# MidiMon.net
KiCad netlist of a schematic drawn in EAGLE
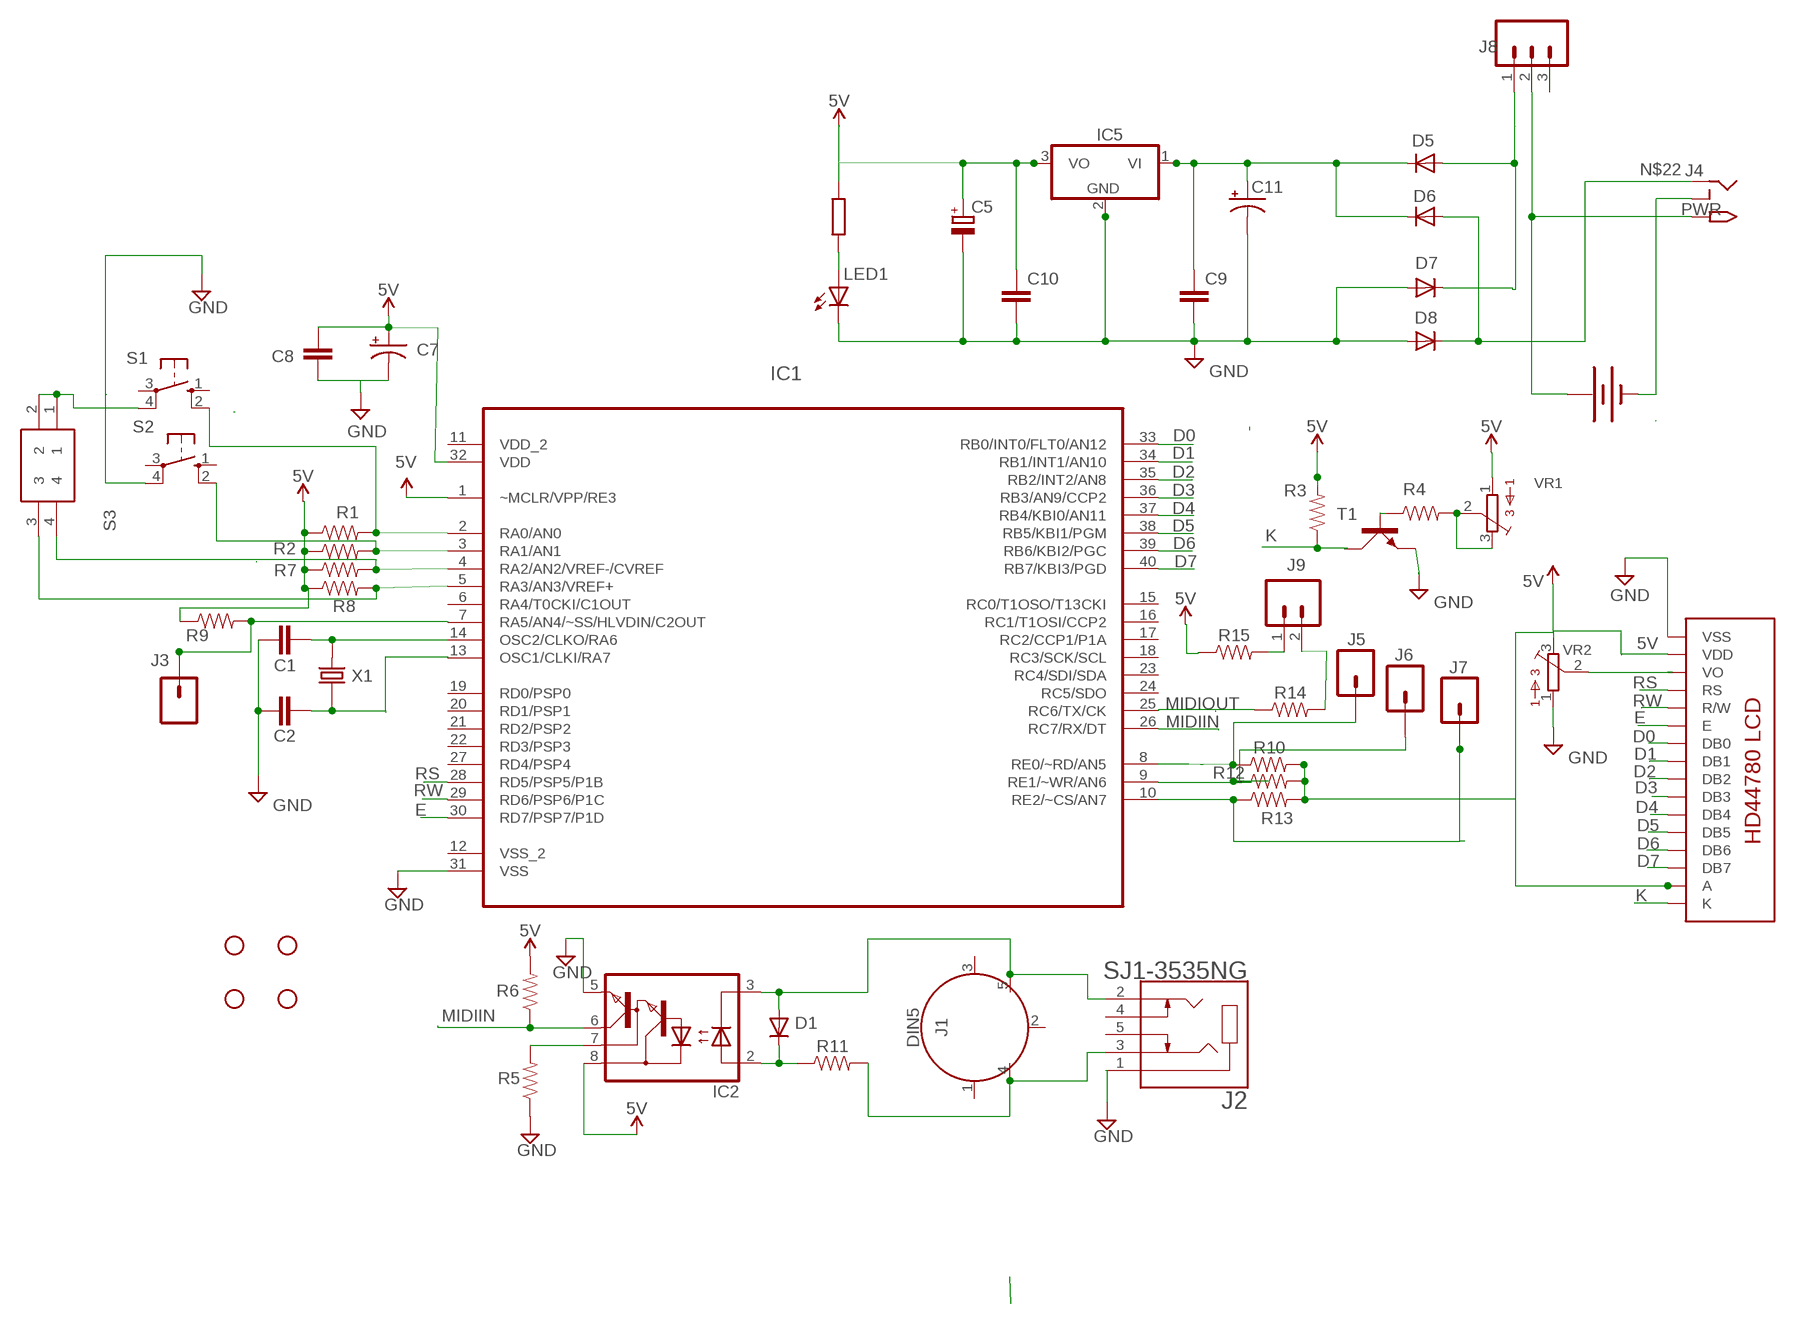
[diagram p0: schematic, sheet 1]

(export (version "E")
  (design (tool "Eeschema 10.0.6"))
  (components
    (comp (ref "BAT1")
      (value "BATTERY")
      (footprint "eagle-import:PP3_BATTERBOX")
      (libsource (lib "eagle-import") (part "BATTERY"))
    )
    (comp (ref "C1")
      (value "33pF")
      (footprint "eagle-import:CAP-PTH-2.54")
      (libsource (lib "eagle-import") (part "22PF-PTH-2.54MM-200V-5%"))
    )
    (comp (ref "C2")
      (value "33pF")
      (footprint "eagle-import:CAP-PTH-2.54")
      (libsource (lib "eagle-import") (part "22PF-PTH-2.54MM-200V-5%"))
    )
    (comp (ref "C5")
      (value "10uf")
      (footprint "eagle-import:E2,5-7")
      (libsource (lib "eagle-import") (part "CPOL-EUE2.5-7"))
    )
    (comp (ref "C7")
      (value "10uF")
      (footprint "eagle-import:CPOL-RADIAL-2.5MM-5MM")
      (libsource (lib "eagle-import") (part "10UF-POLAR-RADIAL-2.5MM-25V-20%"))
    )
    (comp (ref "C8")
      (value "0.1uF")
      (footprint "eagle-import:CAP-PTH-SMALL-KIT")
      (libsource (lib "eagle-import") (part "0.1UF-KIT-EZ-50V-20%"))
    )
    (comp (ref "C9")
      (value "330nf")
      (footprint "eagle-import:C025-024X044")
      (libsource (lib "eagle-import") (part "C-EU025-024X044"))
    )
    (comp (ref "C10")
      (value "100nf")
      (footprint "eagle-import:C025-024X044")
      (libsource (lib "eagle-import") (part "C-EU025-024X044"))
    )
    (comp (ref "C11")
      (value "2200uf")
      (footprint "eagle-import:E5-10,5")
      (libsource (lib "eagle-import") (part "CPOL-USE5-10.5"))
    )
    (comp (ref "D1")
      (value "DIODEDO-1N4148")
      (footprint "eagle-import:DO-1N4148")
      (libsource (lib "eagle-import") (part "DIODEDO-1N4148"))
    )
    (comp (ref "D5")
      (value "1N4004")
      (footprint "eagle-import:DO-VERT")
      (libsource (lib "eagle-import") (part "1N4004"))
    )
    (comp (ref "D6")
      (value "1N4004")
      (footprint "eagle-import:DO-VERT")
      (libsource (lib "eagle-import") (part "1N4004"))
    )
    (comp (ref "D7")
      (value "1N4004")
      (footprint "eagle-import:DO-VERT")
      (libsource (lib "eagle-import") (part "1N4004"))
    )
    (comp (ref "D8")
      (value "1N4004")
      (footprint "eagle-import:DO-VERT")
      (libsource (lib "eagle-import") (part "1N4004"))
    )
    (comp (ref "H1")
      (value "STAND-OFFTIGHT")
      (footprint "eagle-import:STAND-OFF-TIGHT")
      (libsource (lib "eagle-import") (part "STAND-OFFTIGHT"))
    )
    (comp (ref "H2")
      (value "STAND-OFFTIGHT")
      (footprint "eagle-import:STAND-OFF-TIGHT")
      (libsource (lib "eagle-import") (part "STAND-OFFTIGHT"))
    )
    (comp (ref "H3")
      (value "STAND-OFFTIGHT")
      (footprint "eagle-import:STAND-OFF-TIGHT")
      (libsource (lib "eagle-import") (part "STAND-OFFTIGHT"))
    )
    (comp (ref "H4")
      (value "STAND-OFFTIGHT")
      (footprint "eagle-import:STAND-OFF-TIGHT")
      (libsource (lib "eagle-import") (part "STAND-OFFTIGHT"))
    )
    (comp (ref "IC1")
      (value "PIC18F4520-I/P")
      (footprint "eagle-import:DIP254P1524X533-40")
      (fields (field (name "MF") "Microchip"))
      (libsource (lib "eagle-import") (part "PIC18F4520-I/P"))
    )
    (comp (ref "IC2")
      (value "6N138")
      (footprint "eagle-import:DIL08")
      (fields (field (name "MF") "VISHAY/TELEFUNKEN"))
      (libsource (lib "eagle-import") (part "6N138"))
    )
    (comp (ref "IC5")
      (value "7805TV")
      (footprint "eagle-import:TO220V")
      (libsource (lib "eagle-import") (part "78TV05"))
    )
    (comp (ref "J1")
      (value "DIN5")
      (footprint "eagle-import:DIN5-RA-PTH")
      (libsource (lib "eagle-import") (part "DIN5"))
    )
    (comp (ref "J2")
      (value "SJ1-3535NG")
      (footprint "eagle-import:CUI_SJ1-3535NG")
      (fields (field (name "MF") "CUI Inc."))
      (libsource (lib "eagle-import") (part "SJ1-3535NG"))
    )
    (comp (ref "J3")
      (value "CONN_01")
      (footprint "eagle-import:1X01")
      (libsource (lib "eagle-import") (part "CONN_01"))
    )
    (comp (ref "J4")
      (value "2.1MMJACKTHM")
      (footprint "eagle-import:PJ-102A")
      (libsource (lib "eagle-import") (part "2.1MMJACKTHM"))
    )
    (comp (ref "J5")
      (value "CONN_01")
      (footprint "eagle-import:1X01")
      (libsource (lib "eagle-import") (part "CONN_01"))
    )
    (comp (ref "J6")
      (value "CONN_01")
      (footprint "eagle-import:1X01")
      (libsource (lib "eagle-import") (part "CONN_01"))
    )
    (comp (ref "J7")
      (value "CONN_01")
      (footprint "eagle-import:1X01")
      (libsource (lib "eagle-import") (part "CONN_01"))
    )
    (comp (ref "J8")
      (value "CONN_03")
      (footprint "eagle-import:1X03")
      (libsource (lib "eagle-import") (part "CONN_03"))
    )
    (comp (ref "J9")
      (value "CONN_02")
      (footprint "eagle-import:1X02")
      (libsource (lib "eagle-import") (part "CONN_02"))
    )
    (comp (ref "LED1")
      (value "LED3MM")
      (footprint "eagle-import:LED3MM")
      (libsource (lib "eagle-import") (part "LED3MM"))
    )
    (comp (ref "R1")
      (value "10k")
      (footprint "eagle-import:AXIAL-0.3")
      (libsource (lib "eagle-import") (part "1KOHM-HORIZ-1/4W-5%"))
    )
    (comp (ref "R2")
      (value "10k")
      (footprint "eagle-import:AXIAL-0.3")
      (libsource (lib "eagle-import") (part "1KOHM-HORIZ-1/4W-5%"))
    )
    (comp (ref "R3")
      (value "10k")
      (footprint "eagle-import:AXIAL-0.3")
      (libsource (lib "eagle-import") (part "1KOHM-HORIZ-1/4W-5%"))
    )
    (comp (ref "R4")
      (value "1k")
      (footprint "eagle-import:AXIAL-0.3")
      (libsource (lib "eagle-import") (part "1KOHM-HORIZ-1/4W-5%"))
    )
    (comp (ref "R5")
      (value "5.6k")
      (footprint "eagle-import:AXIAL-0.3")
      (libsource (lib "eagle-import") (part "1KOHM-HORIZ-1/4W-5%"))
    )
    (comp (ref "R6")
      (value "1.2k")
      (footprint "eagle-import:AXIAL-0.3")
      (libsource (lib "eagle-import") (part "1KOHM-HORIZ-1/4W-5%"))
    )
    (comp (ref "R7")
      (value "10k")
      (footprint "eagle-import:AXIAL-0.3")
      (libsource (lib "eagle-import") (part "1KOHM-HORIZ-1/4W-5%"))
    )
    (comp (ref "R8")
      (value "10k")
      (footprint "eagle-import:AXIAL-0.3")
      (libsource (lib "eagle-import") (part "1KOHM-HORIZ-1/4W-5%"))
    )
    (comp (ref "R9")
      (value "10k")
      (footprint "eagle-import:AXIAL-0.3")
      (libsource (lib "eagle-import") (part "1KOHM-HORIZ-1/4W-5%"))
    )
    (comp (ref "R10")
      (value "10k")
      (footprint "eagle-import:AXIAL-0.3")
      (libsource (lib "eagle-import") (part "1KOHM-HORIZ-1/4W-5%"))
    )
    (comp (ref "R11")
      (value "220")
      (footprint "eagle-import:AXIAL-0.3")
      (libsource (lib "eagle-import") (part "1KOHM-HORIZ-1/4W-5%"))
    )
    (comp (ref "R12")
      (value "10k")
      (footprint "eagle-import:AXIAL-0.3")
      (libsource (lib "eagle-import") (part "1KOHM-HORIZ-1/4W-5%"))
    )
    (comp (ref "R13")
      (value "10k")
      (footprint "eagle-import:AXIAL-0.3")
      (libsource (lib "eagle-import") (part "1KOHM-HORIZ-1/4W-5%"))
    )
    (comp (ref "R14")
      (value "220")
      (footprint "eagle-import:AXIAL-0.3")
      (libsource (lib "eagle-import") (part "1KOHM-HORIZ-1/4W-5%"))
    )
    (comp (ref "R15")
      (value "220")
      (footprint "eagle-import:AXIAL-0.3")
      (libsource (lib "eagle-import") (part "1KOHM-HORIZ-1/4W-5%"))
    )
    (comp (ref "R20")
      (value "1k")
      (footprint "eagle-import:0207_7")
      (libsource (lib "eagle-import") (part "R-EU_0207/7"))
    )
    (comp (ref "S1")
      (value "40-XX")
      (footprint "eagle-import:B3F-40XX")
      (fields (field (name "MF") "OMRON COMPONENTS USA") (field (name "MPN") "B3F-4000"))
      (libsource (lib "eagle-import") (part "40-XX"))
    )
    (comp (ref "S2")
      (value "40-XX")
      (footprint "eagle-import:B3F-40XX")
      (fields (field (name "MF") "OMRON COMPONENTS USA") (field (name "MPN") "B3F-4000"))
      (libsource (lib "eagle-import") (part "40-XX"))
    )
    (comp (ref "S3")
      (value "195-2MST")
      (footprint "eagle-import:DIPS774W56P254L726H790Q4N")
      (fields (field (name "MOUSER_PART_NUMBER") "774-1952MST"))
      (libsource (lib "eagle-import") (part "195-2MST"))
    )
    (comp (ref "T1")
      (value "2N3904")
      (footprint "eagle-import:TO92D")
      (libsource (lib "eagle-import") (part "2N3904"))
    )
    (comp (ref "U$2")
      (value "LCD-HD4478020X4-3HOLES")
      (footprint "eagle-import:LCD-20X4-3HOLES")
      (libsource (lib "eagle-import") (part "LCD-HD4478020X4-3HOLES"))
    )
    (comp (ref "VR1")
      (value "BOURNS_3362P_TRIMMERP")
      (footprint "eagle-import:BOURNS_3362P_TRIMMER")
      (libsource (lib "eagle-import") (part "BOURNS_3362P_TRIMMERP"))
    )
    (comp (ref "VR2")
      (value "BOURNS_3362P_TRIMMERP")
      (footprint "eagle-import:BOURNS_3362P_TRIMMER")
      (libsource (lib "eagle-import") (part "BOURNS_3362P_TRIMMERP"))
    )
    (comp (ref "X1")
      (value "ECS-100-18-4X")
      (footprint "eagle-import:XTAL_ECS-100-18-4X")
      (fields (field (name "DIGI-KEY_PART_NUMBER") "X1080-ND") (field (name "MF") "ECS Inc."))
      (libsource (lib "eagle-import") (part "ECS-100-18-4X"))
    )
  )
  (nets
    (net (code "1") (name "/D0") (class "Default")
      (node (ref "IC1") (pin "33") (pinfunction "RB0/INT0/FLT0/AN12_33") (pintype "bidirectional"))
      (node (ref "U$2") (pin "P$7") (pinfunction "DB0_P$7") (pintype "bidirectional"))
    )
    (net (code "2") (name "/D1") (class "Default")
      (node (ref "IC1") (pin "34") (pinfunction "RB1/INT1/AN10_34") (pintype "bidirectional"))
      (node (ref "U$2") (pin "P$8") (pinfunction "DB1_P$8") (pintype "bidirectional"))
    )
    (net (code "3") (name "/D2") (class "Default")
      (node (ref "IC1") (pin "35") (pinfunction "RB2/INT2/AN8_35") (pintype "bidirectional"))
      (node (ref "U$2") (pin "P$9") (pinfunction "DB2_P$9") (pintype "bidirectional"))
    )
    (net (code "4") (name "/D3") (class "Default")
      (node (ref "IC1") (pin "36") (pinfunction "RB3/AN9/CCP2_36") (pintype "bidirectional"))
      (node (ref "U$2") (pin "P$10") (pinfunction "DB3_P$10") (pintype "bidirectional"))
    )
    (net (code "5") (name "/D4") (class "Default")
      (node (ref "IC1") (pin "37") (pinfunction "RB4/KBI0/AN11_37") (pintype "bidirectional"))
      (node (ref "U$2") (pin "P$11") (pinfunction "DB4_P$11") (pintype "bidirectional"))
    )
    (net (code "6") (name "/D5") (class "Default")
      (node (ref "IC1") (pin "38") (pinfunction "RB5/KBI1/PGM_38") (pintype "bidirectional"))
      (node (ref "U$2") (pin "P$12") (pinfunction "DB5_P$12") (pintype "bidirectional"))
    )
    (net (code "7") (name "/D6") (class "Default")
      (node (ref "IC1") (pin "39") (pinfunction "RB6/KBI2/PGC_39") (pintype "bidirectional"))
      (node (ref "U$2") (pin "P$13") (pinfunction "DB6_P$13") (pintype "bidirectional"))
    )
    (net (code "8") (name "/D7") (class "Default")
      (node (ref "IC1") (pin "40") (pinfunction "RB7/KBI3/PGD_40") (pintype "bidirectional"))
      (node (ref "U$2") (pin "P$14") (pinfunction "DB7_P$14") (pintype "bidirectional"))
    )
    (net (code "9") (name "/E") (class "Default")
      (node (ref "IC1") (pin "30") (pinfunction "RD7/PSP7/P1D_30") (pintype "bidirectional"))
      (node (ref "U$2") (pin "P$6") (pinfunction "E_P$6") (pintype "input"))
    )
    (net (code "10") (name "/K") (class "Default")
      (node (ref "R3") (pin "P$1") (pinfunction "1_P$1") (pintype "passive"))
      (node (ref "T1") (pin "C") (pinfunction "C_C") (pintype "passive"))
      (node (ref "U$2") (pin "P$16") (pinfunction "K_P$16") (pintype "power_in"))
    )
    (net (code "11") (name "/MIDIIN") (class "Default")
      (node (ref "IC1") (pin "26") (pinfunction "RC7/RX/DT_26") (pintype "bidirectional"))
      (node (ref "IC2") (pin "6") (pinfunction "VO_6") (pintype "passive"))
      (node (ref "R6") (pin "P$1") (pinfunction "1_P$1") (pintype "passive"))
    )
    (net (code "13") (name "/N$22") (class "Default")
      (node (ref "D6") (pin "A") (pinfunction "A_A") (pintype "passive"))
      (node (ref "D8") (pin "C") (pinfunction "C_C") (pintype "passive"))
      (node (ref "J4") (pin "RING") (pinfunction "RING_RING") (pintype "bidirectional"))
    )
    (net (code "14") (name "/PWR") (class "Default")
      (node (ref "BAT1") (pin "9V") (pinfunction "+_9V") (pintype "power_in"))
      (node (ref "J4") (pin "TIP") (pinfunction "TIP_TIP") (pintype "bidirectional"))
      (node (ref "J8") (pin "2") (pinfunction "2_2") (pintype "passive"))
    )
    (net (code "15") (name "/RS") (class "Default")
      (node (ref "IC1") (pin "28") (pinfunction "RD5/PSP5/P1B_28") (pintype "bidirectional"))
      (node (ref "U$2") (pin "P$4") (pinfunction "RS_P$4") (pintype "input"))
    )
    (net (code "16") (name "/RW") (class "Default")
      (node (ref "IC1") (pin "29") (pinfunction "RD6/PSP6/P1C_29") (pintype "bidirectional"))
      (node (ref "U$2") (pin "P$5") (pinfunction "R/W_P$5") (pintype "input"))
    )
    (net (code "17") (name "/VDD_2") (class "Default")
      (node (ref "IC1") (pin "11") (pinfunction "VDD_2_11") (pintype "power_in"))
    )
    (net (code "18") (name "/VSS_2") (class "Default")
      (node (ref "IC1") (pin "12") (pinfunction "VSS_2_12") (pintype "power_in"))
    )
    (net (code "19") (name "5V") (class "Default")
      (node (ref "C10") (pin "1") (pinfunction "1_1") (pintype "passive"))
      (node (ref "C5") (pin "+") (pinfunction "+_+") (pintype "passive"))
      (node (ref "C7") (pin "1") (pinfunction "+_1") (pintype "passive"))
      (node (ref "C8") (pin "2") (pinfunction "2_2") (pintype "passive"))
      (node (ref "IC1") (pin "1") (pinfunction "~{MCLR/VPP/RE3}_1") (pintype "input"))
      (node (ref "IC1") (pin "32") (pinfunction "VDD_32") (pintype "power_in"))
      (node (ref "IC2") (pin "8") (pinfunction "VCC_8") (pintype "passive"))
      (node (ref "IC5") (pin "3") (pinfunction "VO_3") (pintype "passive"))
      (node (ref "R1") (pin "P$1") (pinfunction "1_P$1") (pintype "passive"))
      (node (ref "R10") (pin "P$2") (pinfunction "2_P$2") (pintype "passive"))
      (node (ref "R12") (pin "P$2") (pinfunction "2_P$2") (pintype "passive"))
      (node (ref "R13") (pin "P$2") (pinfunction "2_P$2") (pintype "passive"))
      (node (ref "R15") (pin "P$1") (pinfunction "1_P$1") (pintype "passive"))
      (node (ref "R2") (pin "P$1") (pinfunction "1_P$1") (pintype "passive"))
      (node (ref "R20") (pin "1") (pinfunction "1_1") (pintype "passive"))
      (node (ref "R3") (pin "P$2") (pinfunction "2_P$2") (pintype "passive"))
      (node (ref "R6") (pin "P$2") (pinfunction "2_P$2") (pintype "passive"))
      (node (ref "R7") (pin "P$1") (pinfunction "1_P$1") (pintype "passive"))
      (node (ref "R8") (pin "P$1") (pinfunction "1_P$1") (pintype "passive"))
      (node (ref "R9") (pin "P$1") (pinfunction "1_P$1") (pintype "passive"))
      (node (ref "U$2") (pin "P$15") (pinfunction "A_P$15") (pintype "power_in"))
      (node (ref "U$2") (pin "P$2") (pinfunction "VDD_P$2") (pintype "power_in"))
      (node (ref "VR1") (pin "1") (pinfunction "1_1") (pintype "passive"))
      (node (ref "VR2") (pin "3") (pinfunction "3_3") (pintype "passive"))
    )
    (net (code "20") (name "GND") (class "Default")
      (node (ref "C1") (pin "1") (pinfunction "1_1") (pintype "passive"))
      (node (ref "C10") (pin "2") (pinfunction "2_2") (pintype "passive"))
      (node (ref "C11") (pin "-") (pinfunction "-_-") (pintype "passive"))
      (node (ref "C2") (pin "1") (pinfunction "1_1") (pintype "passive"))
      (node (ref "C5") (pin "-") (pinfunction "-_-") (pintype "passive"))
      (node (ref "C7") (pin "2") (pinfunction "-_2") (pintype "passive"))
      (node (ref "C8") (pin "1") (pinfunction "1_1") (pintype "passive"))
      (node (ref "C9") (pin "2") (pinfunction "2_2") (pintype "passive"))
      (node (ref "D7") (pin "A") (pinfunction "A_A") (pintype "passive"))
      (node (ref "D8") (pin "A") (pinfunction "A_A") (pintype "passive"))
      (node (ref "IC1") (pin "31") (pinfunction "VSS_31") (pintype "power_in"))
      (node (ref "IC2") (pin "5") (pinfunction "GND_5") (pintype "passive"))
      (node (ref "IC5") (pin "2") (pinfunction "GND_2") (pintype "passive"))
      (node (ref "J2") (pin "1") (pinfunction "1_1") (pintype "passive"))
      (node (ref "LED1") (pin "K") (pinfunction "C_K") (pintype "passive"))
      (node (ref "R5") (pin "P$1") (pinfunction "1_P$1") (pintype "passive"))
      (node (ref "S1") (pin "4") (pinfunction "P1_4") (pintype "passive"))
      (node (ref "S2") (pin "4") (pinfunction "P1_4") (pintype "passive"))
      (node (ref "S3") (pin "1") (pinfunction "1_1") (pintype "bidirectional"))
      (node (ref "S3") (pin "2") (pinfunction "2_2") (pintype "bidirectional"))
      (node (ref "T1") (pin "E") (pinfunction "E_E") (pintype "passive"))
      (node (ref "U$2") (pin "P$1") (pinfunction "VSS_P$1") (pintype "power_in"))
      (node (ref "VR2") (pin "1") (pinfunction "1_1") (pintype "passive"))
    )
    (net (code "21") (name "Net-(BAT1--)") (class "Default")
      (node (ref "BAT1") (pin "0V") (pinfunction "-_0V") (pintype "power_in"))
      (node (ref "J4") (pin "RING_SW") (pinfunction "RING_SW_RING_SW") (pintype "bidirectional"))
    )
    (net (code "22") (name "Net-(D5-PadA)") (class "Default")
      (node (ref "D5") (pin "A") (pinfunction "A_A") (pintype "passive"))
      (node (ref "D7") (pin "C") (pinfunction "C_C") (pintype "passive"))
      (node (ref "J8") (pin "1") (pinfunction "1_1") (pintype "passive"))
    )
    (net (code "23") (name "Net-(IC1-OSC1{slash}CLKI{slash}RA7)") (class "Default")
      (node (ref "C2") (pin "2") (pinfunction "2_2") (pintype "passive"))
      (node (ref "IC1") (pin "13") (pinfunction "OSC1/CLKI/RA7_13") (pintype "bidirectional"))
      (node (ref "X1") (pin "1") (pinfunction "1_1") (pintype "passive"))
    )
    (net (code "24") (name "Net-(IC1-OSC2{slash}CLKO{slash}RA6)") (class "Default")
      (node (ref "C1") (pin "2") (pinfunction "2_2") (pintype "passive"))
      (node (ref "IC1") (pin "14") (pinfunction "OSC2/CLKO/RA6_14") (pintype "bidirectional"))
      (node (ref "X1") (pin "2") (pinfunction "2_2") (pintype "passive"))
    )
    (net (code "25") (name "Net-(IC1-RA0{slash}AN0)") (class "Default")
      (node (ref "IC1") (pin "2") (pinfunction "RA0/AN0_2") (pintype "bidirectional"))
      (node (ref "R1") (pin "P$2") (pinfunction "2_P$2") (pintype "passive"))
      (node (ref "S1") (pin "2") (pinfunction "S1_2") (pintype "passive"))
    )
    (net (code "26") (name "Net-(IC1-RA1{slash}AN1)") (class "Default")
      (node (ref "IC1") (pin "3") (pinfunction "RA1/AN1_3") (pintype "bidirectional"))
      (node (ref "R2") (pin "P$2") (pinfunction "2_P$2") (pintype "passive"))
      (node (ref "S2") (pin "2") (pinfunction "S1_2") (pintype "passive"))
    )
    (net (code "27") (name "Net-(IC1-RA2{slash}AN2{slash}VREF-{slash}CVREF)") (class "Default")
      (node (ref "IC1") (pin "4") (pinfunction "RA2/AN2/VREF-/CVREF_4") (pintype "bidirectional"))
      (node (ref "R7") (pin "P$2") (pinfunction "2_P$2") (pintype "passive"))
      (node (ref "S3") (pin "4") (pinfunction "4_4") (pintype "bidirectional"))
    )
    (net (code "28") (name "Net-(IC1-RA3{slash}AN3{slash}VREF+)") (class "Default")
      (node (ref "IC1") (pin "5") (pinfunction "RA3/AN3/VREF+_5") (pintype "bidirectional"))
      (node (ref "R8") (pin "P$2") (pinfunction "2_P$2") (pintype "passive"))
      (node (ref "S3") (pin "3") (pinfunction "3_3") (pintype "bidirectional"))
    )
    (net (code "29") (name "Net-(IC1-RA5{slash}AN4{slash}~{SS{slash}HLVDIN{slash}C2OUT})") (class "Default")
      (node (ref "IC1") (pin "7") (pinfunction "RA5/AN4/~{SS/HLVDIN/C2OUT}_7") (pintype "bidirectional"))
      (node (ref "J3") (pin "1") (pinfunction "1_1") (pintype "passive"))
      (node (ref "R9") (pin "P$2") (pinfunction "2_P$2") (pintype "passive"))
    )
    (net (code "30") (name "Net-(IC1-RC6{slash}TX{slash}CK)") (class "Default")
      (node (ref "IC1") (pin "25") (pinfunction "RC6/TX/CK_25") (pintype "bidirectional"))
      (node (ref "R14") (pin "P$1") (pinfunction "1_P$1") (pintype "passive"))
    )
    (net (code "31") (name "Net-(IC1-RE0{slash}~{RD{slash}AN5})") (class "Default")
      (node (ref "IC1") (pin "8") (pinfunction "RE0/~{RD/AN5}_8") (pintype "bidirectional"))
      (node (ref "J5") (pin "1") (pinfunction "1_1") (pintype "passive"))
      (node (ref "R10") (pin "P$1") (pinfunction "1_P$1") (pintype "passive"))
    )
    (net (code "32") (name "Net-(IC1-RE1{slash}~{WR{slash}AN6})") (class "Default")
      (node (ref "IC1") (pin "9") (pinfunction "RE1/~{WR/AN6}_9") (pintype "bidirectional"))
      (node (ref "J6") (pin "1") (pinfunction "1_1") (pintype "passive"))
      (node (ref "R12") (pin "P$1") (pinfunction "1_P$1") (pintype "passive"))
    )
    (net (code "33") (name "Net-(IC1-RE2{slash}~{CS{slash}AN7})") (class "Default")
      (node (ref "IC1") (pin "10") (pinfunction "RE2/~{CS/AN7}_10") (pintype "bidirectional"))
      (node (ref "J7") (pin "1") (pinfunction "1_1") (pintype "passive"))
      (node (ref "R13") (pin "P$1") (pinfunction "1_P$1") (pintype "passive"))
    )
    (net (code "34") (name "Net-(IC2-A)") (class "Default")
      (node (ref "D1") (pin "C") (pinfunction "C_C") (pintype "passive"))
      (node (ref "IC2") (pin "2") (pinfunction "A_2") (pintype "passive"))
      (node (ref "R11") (pin "P$1") (pinfunction "1_P$1") (pintype "passive"))
    )
    (net (code "35") (name "Net-(IC2-C)") (class "Default")
      (node (ref "D1") (pin "A") (pinfunction "A_A") (pintype "passive"))
      (node (ref "IC2") (pin "3") (pinfunction "C_3") (pintype "passive"))
      (node (ref "J1") (pin "5") (pinfunction "5_5") (pintype "bidirectional"))
      (node (ref "J2") (pin "2") (pinfunction "2_2") (pintype "passive"))
    )
    (net (code "36") (name "Net-(IC2-VB)") (class "Default")
      (node (ref "IC2") (pin "7") (pinfunction "VB_7") (pintype "passive"))
      (node (ref "R5") (pin "P$2") (pinfunction "2_P$2") (pintype "passive"))
    )
    (net (code "37") (name "Net-(IC5-VI)") (class "Default")
      (node (ref "C11") (pin "+") (pinfunction "+_+") (pintype "passive"))
      (node (ref "C9") (pin "1") (pinfunction "1_1") (pintype "passive"))
      (node (ref "D5") (pin "C") (pinfunction "C_C") (pintype "passive"))
      (node (ref "D6") (pin "C") (pinfunction "C_C") (pintype "passive"))
      (node (ref "IC5") (pin "1") (pinfunction "VI_1") (pintype "input"))
    )
    (net (code "38") (name "Net-(LED1-PadA)") (class "Default")
      (node (ref "LED1") (pin "A") (pinfunction "A_A") (pintype "passive"))
      (node (ref "R20") (pin "2") (pinfunction "2_2") (pintype "passive"))
    )
    (net (code "39") (name "Net-(R4-1)") (class "Default")
      (node (ref "R4") (pin "P$1") (pinfunction "1_P$1") (pintype "passive"))
      (node (ref "T1") (pin "B") (pinfunction "B_B") (pintype "passive"))
    )
    (net (code "40") (name "Net-(R4-2)") (class "Default")
      (node (ref "R4") (pin "P$2") (pinfunction "2_P$2") (pintype "passive"))
      (node (ref "VR1") (pin "2") (pinfunction "2_2") (pintype "passive"))
      (node (ref "VR1") (pin "3") (pinfunction "3_3") (pintype "passive"))
    )
    (net (code "41") (name "Net-(R11-2)") (class "Default")
      (node (ref "J1") (pin "4") (pinfunction "4_4") (pintype "bidirectional"))
      (node (ref "J2") (pin "3") (pinfunction "3_3") (pintype "passive"))
      (node (ref "R11") (pin "P$2") (pinfunction "2_P$2") (pintype "passive"))
    )
    (net (code "42") (name "Net-(R14-2)") (class "Default")
      (node (ref "J9") (pin "2") (pinfunction "2_2") (pintype "passive"))
      (node (ref "R14") (pin "P$2") (pinfunction "2_P$2") (pintype "passive"))
    )
    (net (code "43") (name "Net-(R15-2)") (class "Default")
      (node (ref "J9") (pin "1") (pinfunction "1_1") (pintype "passive"))
      (node (ref "R15") (pin "P$2") (pinfunction "2_P$2") (pintype "passive"))
    )
    (net (code "44") (name "Net-(U$2-VO)") (class "Default")
      (node (ref "U$2") (pin "P$3") (pinfunction "VO_P$3") (pintype "bidirectional"))
      (node (ref "VR2") (pin "2") (pinfunction "2_2") (pintype "passive"))
    )
    (net (code "45") (name "unconnected-(IC1-RA4{slash}T0CKI{slash}C1OUT-Pad6)") (class "Default")
      (node (ref "IC1") (pin "6") (pinfunction "RA4/T0CKI/C1OUT_6") (pintype "bidirectional"))
    )
    (net (code "46") (name "unconnected-(IC1-RC0{slash}T1OSO{slash}T13CKI-Pad15)") (class "Default")
      (node (ref "IC1") (pin "15") (pinfunction "RC0/T1OSO/T13CKI_15") (pintype "bidirectional"))
    )
    (net (code "47") (name "unconnected-(IC1-RC1{slash}T1OSI{slash}CCP2-Pad16)") (class "Default")
      (node (ref "IC1") (pin "16") (pinfunction "RC1/T1OSI/CCP2_16") (pintype "bidirectional"))
    )
    (net (code "48") (name "unconnected-(IC1-RC2{slash}CCP1{slash}P1A-Pad17)") (class "Default")
      (node (ref "IC1") (pin "17") (pinfunction "RC2/CCP1/P1A_17") (pintype "bidirectional"))
    )
    (net (code "49") (name "unconnected-(IC1-RC3{slash}SCK{slash}SCL-Pad18)") (class "Default")
      (node (ref "IC1") (pin "18") (pinfunction "RC3/SCK/SCL_18") (pintype "bidirectional"))
    )
    (net (code "50") (name "unconnected-(IC1-RC4{slash}SDI{slash}SDA-Pad23)") (class "Default")
      (node (ref "IC1") (pin "23") (pinfunction "RC4/SDI/SDA_23") (pintype "bidirectional"))
    )
    (net (code "51") (name "unconnected-(IC1-RC5{slash}SDO-Pad24)") (class "Default")
      (node (ref "IC1") (pin "24") (pinfunction "RC5/SDO_24") (pintype "bidirectional"))
    )
    (net (code "52") (name "unconnected-(IC1-RD0{slash}PSP0-Pad19)") (class "Default")
      (node (ref "IC1") (pin "19") (pinfunction "RD0/PSP0_19") (pintype "bidirectional"))
    )
    (net (code "53") (name "unconnected-(IC1-RD1{slash}PSP1-Pad20)") (class "Default")
      (node (ref "IC1") (pin "20") (pinfunction "RD1/PSP1_20") (pintype "bidirectional"))
    )
    (net (code "54") (name "unconnected-(IC1-RD2{slash}PSP2-Pad21)") (class "Default")
      (node (ref "IC1") (pin "21") (pinfunction "RD2/PSP2_21") (pintype "bidirectional"))
    )
    (net (code "55") (name "unconnected-(IC1-RD3{slash}PSP3-Pad22)") (class "Default")
      (node (ref "IC1") (pin "22") (pinfunction "RD3/PSP3_22") (pintype "bidirectional"))
    )
    (net (code "56") (name "unconnected-(IC1-RD4{slash}PSP4-Pad27)") (class "Default")
      (node (ref "IC1") (pin "27") (pinfunction "RD4/PSP4_27") (pintype "bidirectional"))
    )
    (net (code "57") (name "unconnected-(J1-Pad1)") (class "Default")
      (node (ref "J1") (pin "1") (pinfunction "1_1") (pintype "bidirectional"))
    )
    (net (code "58") (name "unconnected-(J1-Pad2)") (class "Default")
      (node (ref "J1") (pin "2") (pinfunction "2_2") (pintype "bidirectional"))
    )
    (net (code "59") (name "unconnected-(J1-Pad3)") (class "Default")
      (node (ref "J1") (pin "3") (pinfunction "3_3") (pintype "bidirectional"))
    )
    (net (code "60") (name "unconnected-(J2-Pad4)") (class "Default")
      (node (ref "J2") (pin "4") (pinfunction "4_4") (pintype "passive"))
    )
    (net (code "61") (name "unconnected-(J2-Pad5)") (class "Default")
      (node (ref "J2") (pin "5") (pinfunction "5_5") (pintype "passive"))
    )
    (net (code "62") (name "unconnected-(J8-Pad3)") (class "Default")
      (node (ref "J8") (pin "3") (pinfunction "3_3") (pintype "passive"))
    )
    (net (code "63") (name "unconnected-(S1-P-Pad3)") (class "Default")
      (node (ref "S1") (pin "3") (pinfunction "P_3") (pintype "passive"))
    )
    (net (code "64") (name "unconnected-(S1-S-Pad1)") (class "Default")
      (node (ref "S1") (pin "1") (pinfunction "S_1") (pintype "passive"))
    )
    (net (code "65") (name "unconnected-(S2-P-Pad3)") (class "Default")
      (node (ref "S2") (pin "3") (pinfunction "P_3") (pintype "passive"))
    )
    (net (code "66") (name "unconnected-(S2-S-Pad1)") (class "Default")
      (node (ref "S2") (pin "1") (pinfunction "S_1") (pintype "passive"))
    )
  )
)
